# brake.net
KiCad netlist of a schematic drawn in EasyEDA
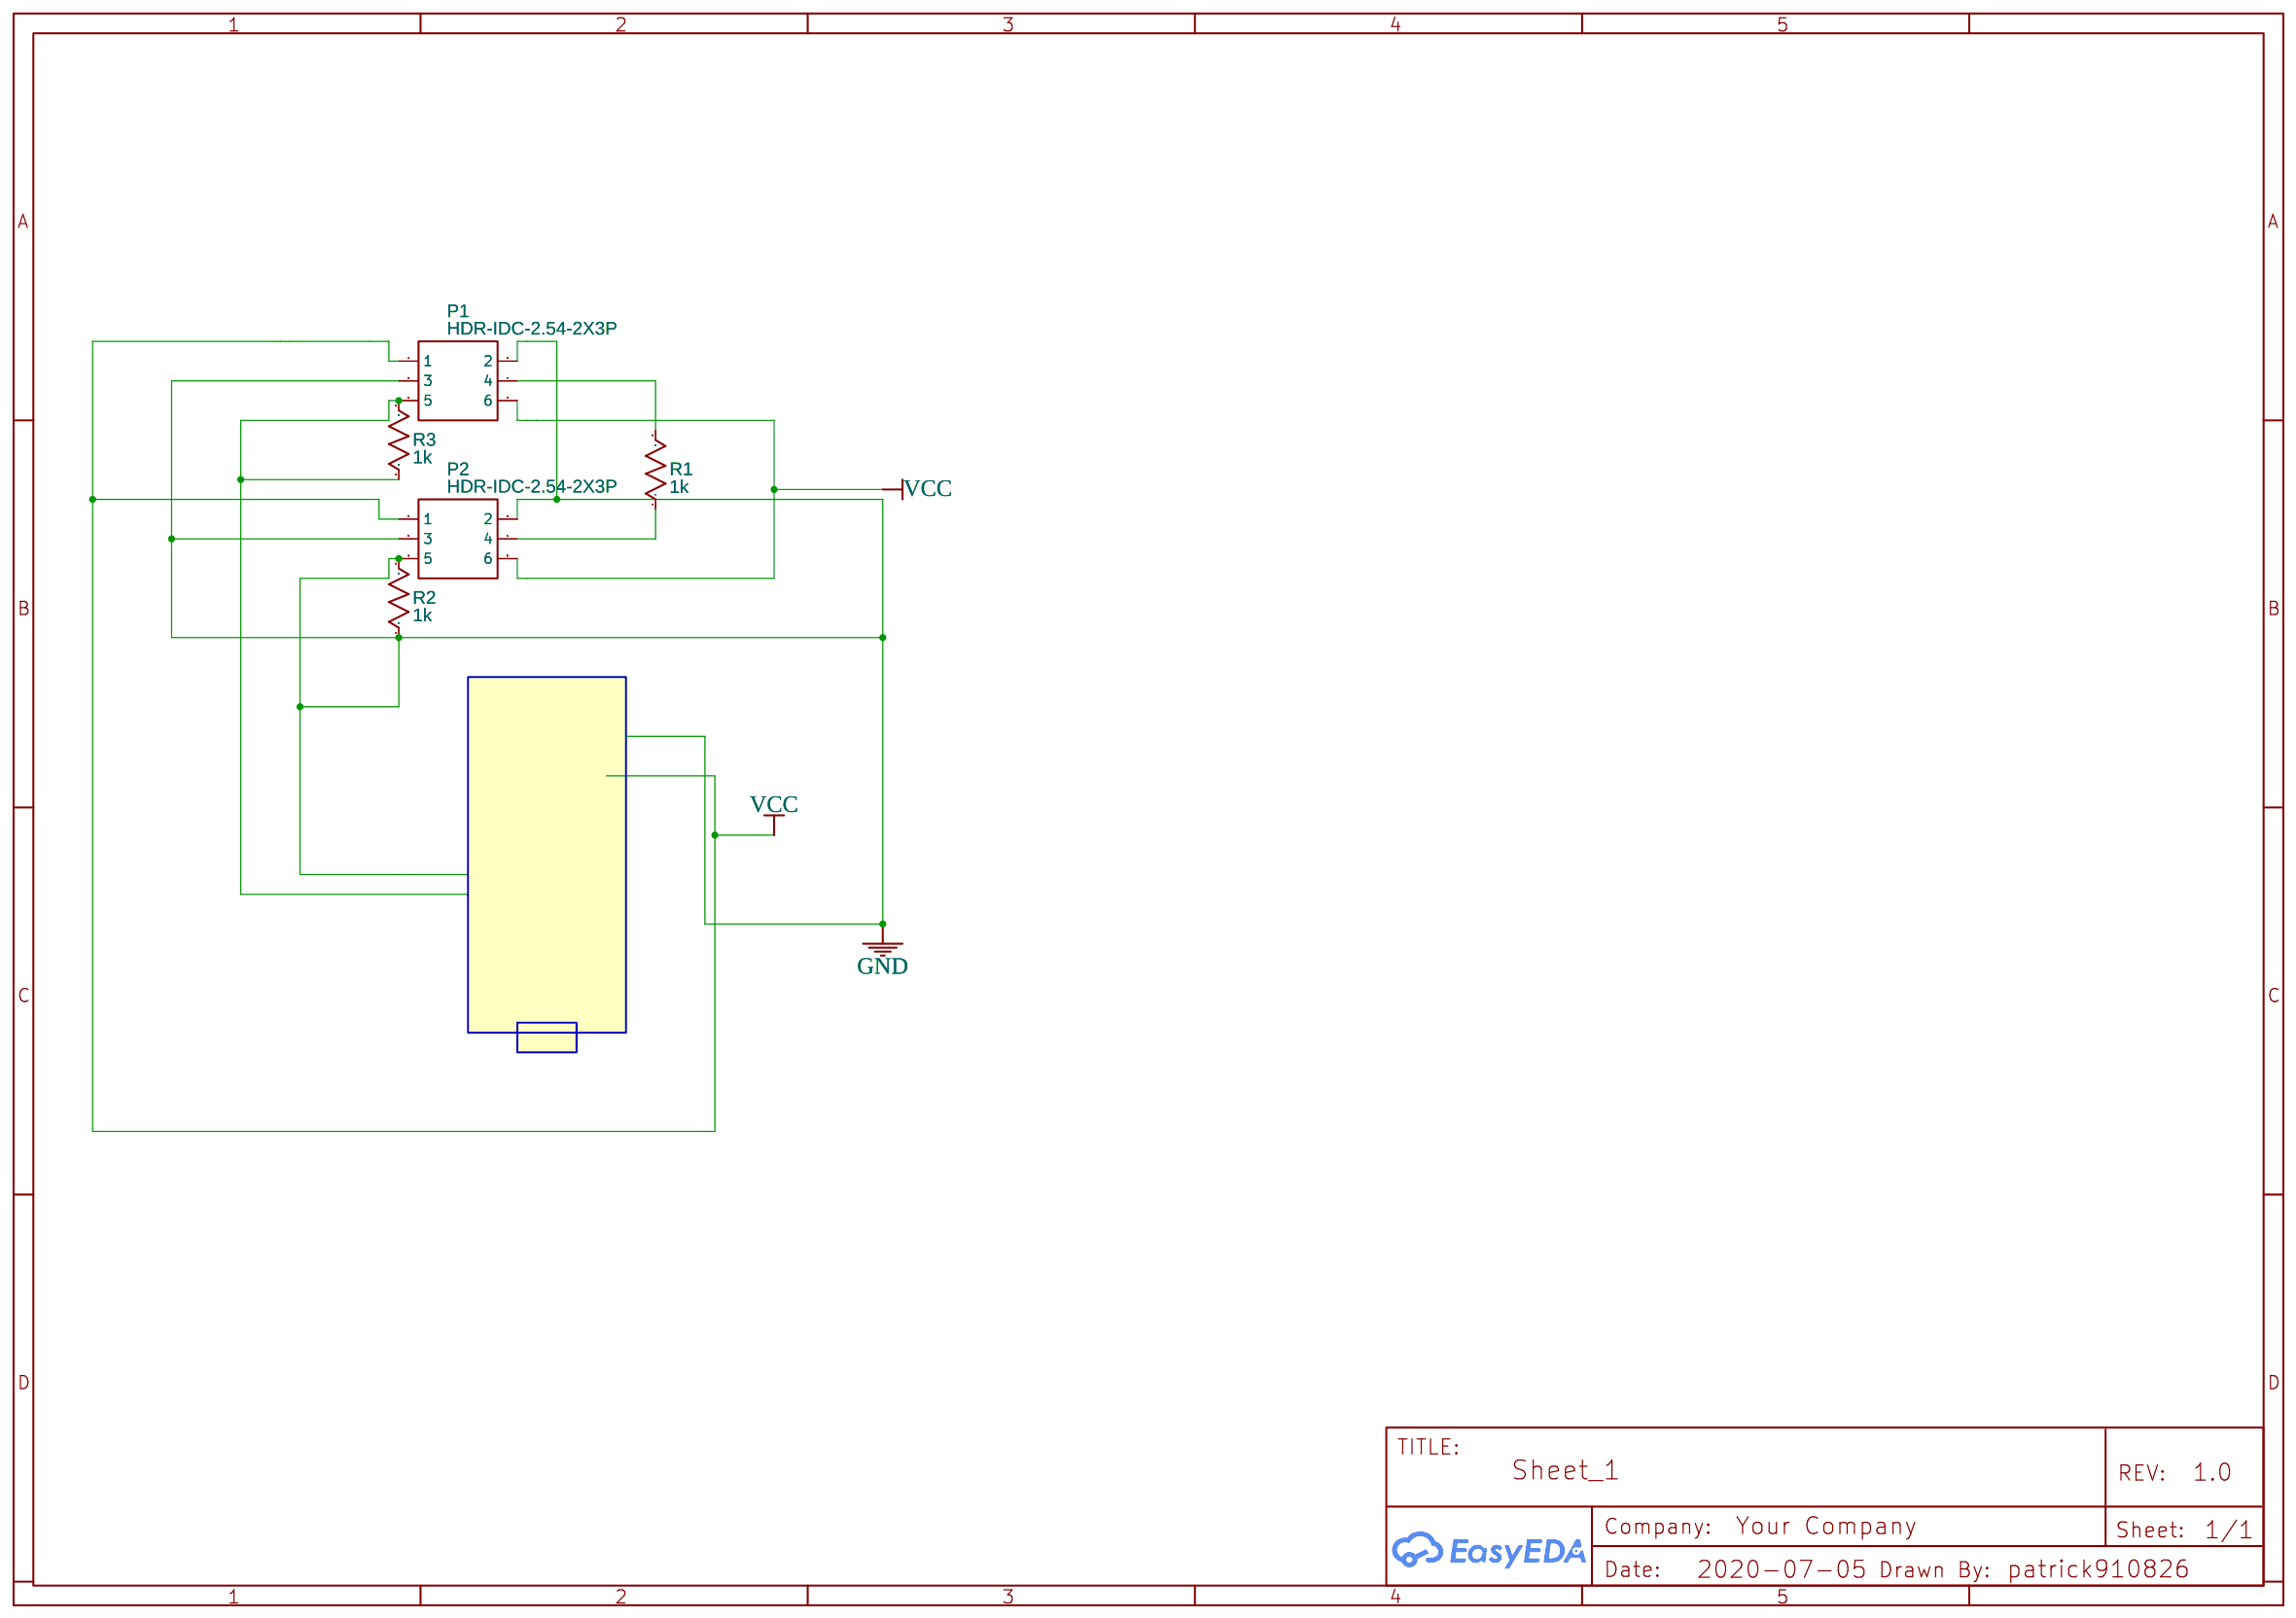
[diagram p0: schematic sheet]

(export (version "E")
  (design (tool "Eeschema 10.0.6"))
  (components
    (comp (ref "P1")
      (value "HDR-IDC-2.54-2X3P")
      (fields
        (field (name "BOM_Manufacturer Part") "2X3 2.54mm IDC Box")
        (field (name "BOM_Supplier Part") "C11214")
      )
      (libsource (lib "") (part "HDR-IDC-2.54-2X3P"))
    )
    (comp (ref "P2")
      (value "HDR-IDC-2.54-2X3P")
      (fields
        (field (name "BOM_Manufacturer Part") "2X3 2.54mm IDC Box")
        (field (name "BOM_Supplier Part") "C11214")
      )
      (libsource (lib "") (part "HDR-IDC-2.54-2X3P"))
    )
    (comp (ref "R1") (value "1k") (libsource (lib "") (part "R_AXIAL-0.5_US")))
    (comp (ref "R2") (value "1k") (libsource (lib "") (part "R_AXIAL-0.5_US")))
    (comp (ref "R3") (value "1k") (libsource (lib "") (part "R_AXIAL-0.5_US")))
  )
  (nets
    (net (code "1") (name "GND") (class "Default")
      (node (ref "P1") (pin "2") (pinfunction "2_2") (pintype "unspecified"))
      (node (ref "P1") (pin "3") (pinfunction "3_3") (pintype "unspecified"))
      (node (ref "P2") (pin "2") (pinfunction "2_2") (pintype "unspecified"))
      (node (ref "P2") (pin "3") (pinfunction "3_3") (pintype "unspecified"))
      (node (ref "P2") (pin "5") (pinfunction "5_5") (pintype "unspecified"))
      (node (ref "R2") (pin "1") (pinfunction "1_1") (pintype "unspecified"))
      (node (ref "R2") (pin "2") (pinfunction "2_2") (pintype "unspecified"))
    )
    (net (code "2") (name "Net-(P1-Pad4)") (class "Default")
      (node (ref "P1") (pin "4") (pinfunction "4_4") (pintype "unspecified"))
      (node (ref "R1") (pin "2") (pinfunction "2_2") (pintype "unspecified"))
    )
    (net (code "3") (name "Net-(P1-Pad5)") (class "Default")
      (node (ref "P1") (pin "5") (pinfunction "5_5") (pintype "unspecified"))
      (node (ref "R3") (pin "1") (pinfunction "1_1") (pintype "unspecified"))
      (node (ref "R3") (pin "2") (pinfunction "2_2") (pintype "unspecified"))
    )
    (net (code "4") (name "Net-(P2-Pad4)") (class "Default")
      (node (ref "P2") (pin "4") (pinfunction "4_4") (pintype "unspecified"))
      (node (ref "R1") (pin "1") (pinfunction "1_1") (pintype "unspecified"))
    )
    (net (code "5") (name "VCC") (class "Default")
      (node (ref "P1") (pin "1") (pinfunction "1_1") (pintype "unspecified"))
      (node (ref "P1") (pin "6") (pinfunction "6_6") (pintype "unspecified"))
      (node (ref "P2") (pin "1") (pinfunction "1_1") (pintype "unspecified"))
      (node (ref "P2") (pin "6") (pinfunction "6_6") (pintype "unspecified"))
    )
  )
)
